# FTDI_USB.net
KiCad netlist of a schematic drawn in Altium Designer
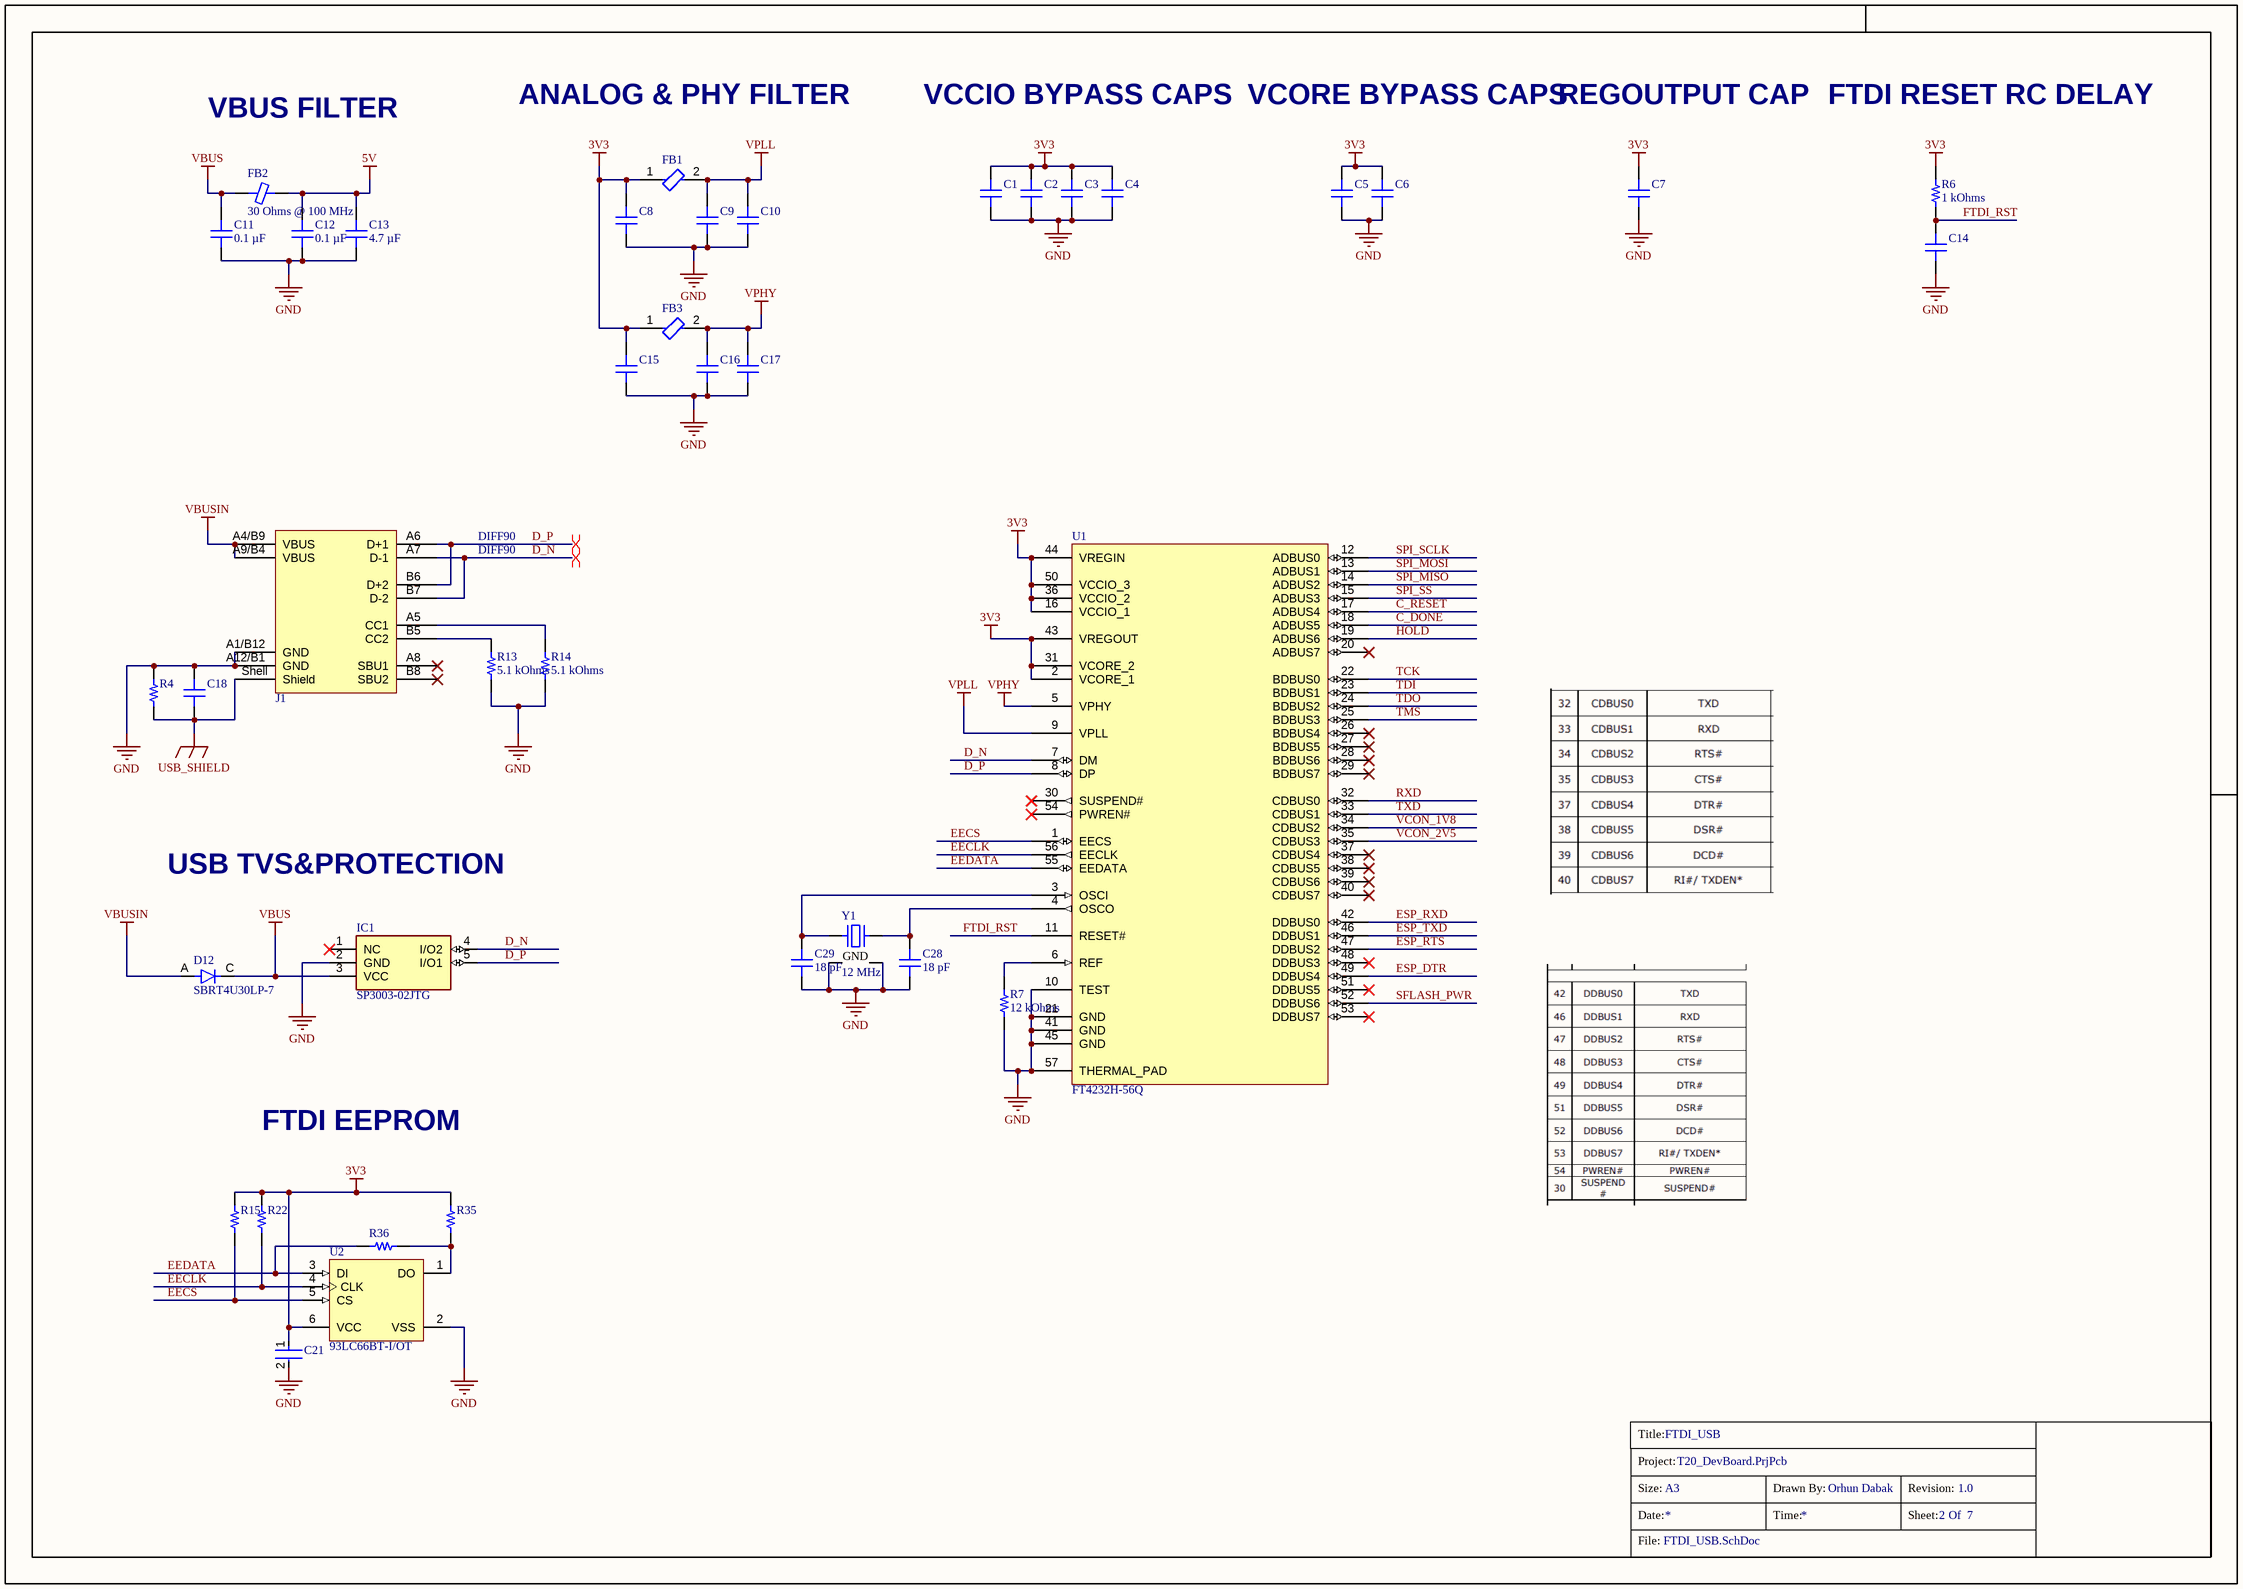
[diagram p0: FTDI_USB.SchDoc]

(export (version "E")
  (design (tool "Eeschema 10.0.6"))
  (components
    (comp (ref "C1")
      (value "0.1 µF")
      (footprint "CAP 0402_1005")
      (description "CAP CER 0.1UF 10V X7R 0402")
      (fields (field (name "PART NUMBER") "CC0402KRX7R6BB104") (field (name "MANUFACTURER") "Yageo"))
      (libsource (lib "Celestial Altium Library - altium_library") (part "Capacitor"))
    )
    (comp (ref "C2")
      (value "0.1 µF")
      (footprint "CAP 0402_1005")
      (description "CAP CER 0.1UF 10V X7R 0402")
      (fields (field (name "PART NUMBER") "CC0402KRX7R6BB104") (field (name "MANUFACTURER") "Yageo"))
      (libsource (lib "Celestial Altium Library - altium_library") (part "Capacitor"))
    )
    (comp (ref "C3")
      (value "0.1 µF")
      (footprint "CAP 0402_1005")
      (description "CAP CER 0.1UF 10V X7R 0402")
      (fields (field (name "PART NUMBER") "CC0402KRX7R6BB104") (field (name "MANUFACTURER") "Yageo"))
      (libsource (lib "Celestial Altium Library - altium_library") (part "Capacitor"))
    )
    (comp (ref "C4")
      (value "0.1 µF")
      (footprint "CAP 0402_1005")
      (description "CAP CER 0.1UF 10V X7R 0402")
      (fields (field (name "PART NUMBER") "CC0402KRX7R6BB104") (field (name "MANUFACTURER") "Yageo"))
      (libsource (lib "Celestial Altium Library - altium_library") (part "Capacitor"))
    )
    (comp (ref "C5")
      (value "0.1 µF")
      (footprint "CAP 0402_1005")
      (description "CAP CER 0.1UF 10V X7R 0402")
      (fields (field (name "PART NUMBER") "CC0402KRX7R6BB104") (field (name "MANUFACTURER") "Yageo"))
      (libsource (lib "Celestial Altium Library - altium_library") (part "Capacitor"))
    )
    (comp (ref "C6")
      (value "0.1 µF")
      (footprint "CAP 0402_1005")
      (description "CAP CER 0.1UF 10V X7R 0402")
      (fields (field (name "PART NUMBER") "CC0402KRX7R6BB104") (field (name "MANUFACTURER") "Yageo"))
      (libsource (lib "Celestial Altium Library - altium_library") (part "Capacitor"))
    )
    (comp (ref "C7")
      (value "4.7 µF")
      (footprint "CAP 0402_1005")
      (description "CAP CER 4.7UF 10V X5R 0402")
      (fields
        (field (name "PART NUMBER") "CL05A475MP5NRNC")
        (field (name "MANUFACTURER") "Samsung Electro-Mechanics")
      )
      (libsource (lib "Celestial Altium Library - altium_library") (part "Capacitor"))
    )
    (comp (ref "C8")
      (value "0.1 µF")
      (footprint "CAP 0402_1005")
      (description "CAP CER 0.1UF 10V X7R 0402")
      (fields (field (name "PART NUMBER") "CC0402KRX7R6BB104") (field (name "MANUFACTURER") "Yageo"))
      (libsource (lib "Celestial Altium Library - altium_library") (part "Capacitor"))
    )
    (comp (ref "C9")
      (value "0.1 µF")
      (footprint "CAP 0402_1005")
      (description "CAP CER 0.1UF 10V X7R 0402")
      (fields (field (name "PART NUMBER") "CC0402KRX7R6BB104") (field (name "MANUFACTURER") "Yageo"))
      (libsource (lib "Celestial Altium Library - altium_library") (part "Capacitor"))
    )
    (comp (ref "C10")
      (value "4.7 µF")
      (footprint "CAP 0402_1005")
      (description "CAP CER 4.7UF 10V X5R 0402")
      (fields
        (field (name "PART NUMBER") "CL05A475MP5NRNC")
        (field (name "MANUFACTURER") "Samsung Electro-Mechanics")
      )
      (libsource (lib "Celestial Altium Library - altium_library") (part "Capacitor"))
    )
    (comp (ref "C11")
      (value "0.1 µF")
      (footprint "CAP 0603_1608")
      (description "CAP CER 0.1UF 25V X7R 0603")
      (fields (field (name "PART NUMBER") "C0603X104M3RAC7867") (field (name "MANUFACTURER") "KEMET"))
      (libsource (lib "Celestial Altium Library - altium_library") (part "Capacitor"))
    )
    (comp (ref "C12")
      (value "0.1 µF")
      (footprint "CAP 0603_1608")
      (description "CAP CER 0.1UF 25V X7R 0603")
      (fields (field (name "PART NUMBER") "C0603X104M3RAC7867") (field (name "MANUFACTURER") "KEMET"))
      (libsource (lib "Celestial Altium Library - altium_library") (part "Capacitor"))
    )
    (comp (ref "C13")
      (value "4.7 µF")
      (footprint "CAP 0603_1608")
      (description "CAP CER 4.7UF 25V X5R 0603")
      (fields
        (field (name "PART NUMBER") "CL10A475KA8NQNC")
        (field (name "MANUFACTURER") "Samsung Electro-Mechanics")
      )
      (libsource (lib "Celestial Altium Library - altium_library") (part "Capacitor"))
    )
    (comp (ref "C14")
      (value "0.1 µF")
      (footprint "CAP 0402_1005")
      (description "CAP CER 0.1UF 10V X7R 0402")
      (fields (field (name "PART NUMBER") "CC0402KRX7R6BB104") (field (name "MANUFACTURER") "Yageo"))
      (libsource (lib "Celestial Altium Library - altium_library") (part "Capacitor"))
    )
    (comp (ref "C15")
      (value "0.1 µF")
      (footprint "CAP 0402_1005")
      (description "CAP CER 0.1UF 10V X7R 0402")
      (fields (field (name "PART NUMBER") "CC0402KRX7R6BB104") (field (name "MANUFACTURER") "Yageo"))
      (libsource (lib "Celestial Altium Library - altium_library") (part "Capacitor"))
    )
    (comp (ref "C16")
      (value "0.1 µF")
      (footprint "CAP 0402_1005")
      (description "CAP CER 0.1UF 10V X7R 0402")
      (fields (field (name "PART NUMBER") "CC0402KRX7R6BB104") (field (name "MANUFACTURER") "Yageo"))
      (libsource (lib "Celestial Altium Library - altium_library") (part "Capacitor"))
    )
    (comp (ref "C17")
      (value "4.7 µF")
      (footprint "CAP 0402_1005")
      (description "CAP CER 4.7UF 10V X5R 0402")
      (fields
        (field (name "PART NUMBER") "CL05A475MP5NRNC")
        (field (name "MANUFACTURER") "Samsung Electro-Mechanics")
      )
      (libsource (lib "Celestial Altium Library - altium_library") (part "Capacitor"))
    )
    (comp (ref "C18")
      (value "10000 pF")
      (footprint "CAP 0402_1005")
      (description "CAP CER 10000PF 100V X7R 0402")
      (fields (field (name "PART NUMBER") "CC0402KRX7R0BB103") (field (name "MANUFACTURER") "Yageo"))
      (libsource (lib "Celestial Altium Library - altium_library") (part "Capacitor"))
    )
    (comp (ref "C21")
      (value "EMK105B7104KV-F")
      (footprint "FP-0402-L_1_0_0_05-W_0_5-MFG")
      (description "None")
      (fields (field (name "TOLERANCE") "10%"))
      (libsource (lib "Altium Content Vault") (part "b4654b650e69147ec39a6b967a45e02"))
    )
    (comp (ref "C28")
      (value "18 pF")
      (footprint "CAP 0402_1005")
      (description "CAP CER 18PF 50V C0G/NP0 0402")
      (fields (field (name "PART NUMBER") "C0402C180J5GACAUTO") (field (name "MANUFACTURER") "KEMET"))
      (libsource (lib "Celestial Altium Library - altium_library") (part "Capacitor"))
    )
    (comp (ref "C29")
      (value "18 pF")
      (footprint "CAP 0402_1005")
      (description "CAP CER 18PF 50V C0G/NP0 0402")
      (fields (field (name "PART NUMBER") "C0402C180J5GACAUTO") (field (name "MANUFACTURER") "KEMET"))
      (libsource (lib "Celestial Altium Library - altium_library") (part "Capacitor"))
    )
    (comp (ref "D12")
      (value "SBRT4U30LP-7")
      (footprint "DIO_SBRT4U30LP-7:DIO_SBRT4U30LP-7")
      (description "Diode Super Barrier 30 V 4A Surface Mount U-DFN2020-2")
      (fields (field (name "MF") "Diodes Inc."))
      (libsource (lib "SBRT4U30LP-7") (part "SBRT4U30LP-7"))
    )
    (comp (ref "FB1")
      (value "BLM15AX601SN1D")
      (footprint "FP-BLM15-0_05-IPC_B")
      (description "Chip Ferrite Bead, 0402, 600Ω @ 100MHz, 0.34Ω, 25%, 500mA")
      (fields (field (name "TOLERANCE") "25%"))
      (libsource (lib "Altium Content Vault") (part "5f30dd21d616792df468990f7003faa"))
    )
    (comp (ref "FB2")
      (value "30 Ohms @ 100 MHz")
      (footprint "FER 0805_2012")
      (description "FERRITE BEAD 30 OHM 0805 1LN")
      (fields
        (field (name "PART NUMBER") "BLM21PG300SN1D")
        (field (name "MANUFACTURER") "Murata Electronics")
      )
      (libsource (lib "Celestial Altium Library - altium_library") (part "Ferrite Chip"))
    )
    (comp (ref "FB3")
      (value "BLM15AX601SN1D")
      (footprint "FP-BLM15-0_05-IPC_B")
      (description "Chip Ferrite Bead, 0402, 600Ω @ 100MHz, 0.34Ω, 25%, 500mA")
      (fields (field (name "TOLERANCE") "25%"))
      (libsource (lib "Altium Content Vault") (part "5f30dd21d616792df468990f7003faa"))
    )
    (comp (ref "IC1")
      (value "SP3003-02JTG")
      (footprint "SamacSys:SOT65P220X110-5N")
      (description "Integrated Circuit")
      (fields (field (name "MOUSER PART NUMBER") "576-SP3003-02JTG"))
      (libsource (lib "*") (part "SP3003-02JTG"))
    )
    (comp (ref "J1")
      (value "629722000214")
      (footprint "629722000214")
      (description "WR-USB 2.0 Type C, Receptacle, Horizontal, SMT")
      (fields (field (name "MANUFACTURER") "Wurth Elektronik"))
      (libsource (lib "Altium_WR-USB (rev22b)") (part "629722000214"))
    )
    (comp (ref "R4")
      (value "1 MOhms")
      (footprint "RES 0402_1005")
      (description "RES SMD 1M OHM 1% 1/16W 0402")
      (fields (field (name "PART NUMBER") "AC0402FR-071ML") (field (name "MANUFACTURER") "Yageo"))
      (libsource (lib "Celestial Altium Library - altium_library") (part "Resistor"))
    )
    (comp (ref "R6")
      (value "1 kOhms")
      (footprint "RES 0402_1005")
      (description "RES SMD 1K OHM 5% 1/16W 0402")
      (fields (field (name "PART NUMBER") "RC0402JR-071KP") (field (name "MANUFACTURER") "Yageo"))
      (libsource (lib "Celestial Altium Library - altium_library") (part "Resistor"))
    )
    (comp (ref "R7")
      (value "12 kOhms")
      (footprint "RES 0402_1005")
      (description "RES SMD 12K OHM 0.1% 1/16W 0402")
      (fields
        (field (name "PART NUMBER") "CPF0402B12KE1")
        (field (name "MANUFACTURER") "TE Connectivity Passive Product")
      )
      (libsource (lib "Celestial Altium Library - altium_library") (part "Resistor"))
    )
    (comp (ref "R13")
      (value "5.1 kOhms")
      (footprint "RES 0402_1005")
      (description "RES SMD 5.1K OHM 5% 1/16W 0402")
      (fields (field (name "PART NUMBER") "AC0402JR-075K1L") (field (name "MANUFACTURER") "Yageo"))
      (libsource (lib "Celestial Altium Library - altium_library") (part "Resistor"))
    )
    (comp (ref "R14")
      (value "5.1 kOhms")
      (footprint "RES 0402_1005")
      (description "RES SMD 5.1K OHM 5% 1/16W 0402")
      (fields (field (name "PART NUMBER") "AC0402JR-075K1L") (field (name "MANUFACTURER") "Yageo"))
      (libsource (lib "Celestial Altium Library - altium_library") (part "Resistor"))
    )
    (comp (ref "R15")
      (value "10 kOhms")
      (footprint "RES 0402_1005")
      (description "RES 10K OHM 0.1% 1/10W 0402")
      (fields
        (field (name "PART NUMBER") "RP73PF1E10KBTD")
        (field (name "MANUFACTURER") "TE Connectivity Passive Product")
      )
      (libsource (lib "Celestial Altium Library - altium_library") (part "Resistor"))
    )
    (comp (ref "R22")
      (value "10 kOhms")
      (footprint "RES 0402_1005")
      (description "RES 10K OHM 0.1% 1/10W 0402")
      (fields
        (field (name "PART NUMBER") "RP73PF1E10KBTD")
        (field (name "MANUFACTURER") "TE Connectivity Passive Product")
      )
      (libsource (lib "Celestial Altium Library - altium_library") (part "Resistor"))
    )
    (comp (ref "R35")
      (value "10 kOhms")
      (footprint "RES 0402_1005")
      (description "RES 10K OHM 0.1% 1/10W 0402")
      (fields
        (field (name "PART NUMBER") "RP73PF1E10KBTD")
        (field (name "MANUFACTURER") "TE Connectivity Passive Product")
      )
      (libsource (lib "Celestial Altium Library - altium_library") (part "Resistor"))
    )
    (comp (ref "R36")
      (value "2.2 kOhms")
      (footprint "RES 0402_1005")
      (description "RES 2.2K OHM 0.1% 1/10W 0402")
      (fields (field (name "PART NUMBER") "TNPW04022K20BYEP") (field (name "MANUFACTURER") "Vishay Dale"))
      (libsource (lib "Celestial Altium Library - altium_library") (part "Resistor"))
    )
    (comp (ref "U1")
      (value "FT4232H-56Q")
      (footprint "QFN50P800X800X100-57N-D")
      (description "USB Bridge, USB to UART,FIFO USB 2.0 FIFO Interface 56-VQFN (8x8)")
      (fields (field (name "MANUFACTURER") "FTDI, Future Technology Devices International Ltd"))
      (libsource (lib "T8_devkit_PCB") (part "FT4232H-56Q"))
    )
    (comp (ref "U2")
      (value "93LC66BT-I/OT")
      (footprint "SOT-23-OT6_N")
      (description "Microwire Serial EEPROM Family, 2.5Vto 5.5V' 2 MHz, -40°Cto 125°C, SOT-23-6, RoHS")
      (libsource (lib "Kocaeli University") (part "MEM-SEEPROM-93AA46B-OT-6"))
    )
    (comp (ref "Y1")
      (value "12 MHz")
      (footprint "NDK NX3225GA")
      (description "CRYSTAL 12.0000MHZ 8PF SMD")
      (fields
        (field (name "PART NUMBER") "NX3225GA-12MHZ-STD-CRG-2")
        (field (name "MANUFACTURER") "NDK America, Inc.")
      )
      (libsource (lib "Celestial Altium Library - altium_library") (part "NDK Crystal NX3225GA"))
    )
  )
  (nets
    (net (code "1") (name "/C_DONE") (class "Default")
      (node (ref "U1") (pin "18") (pinfunction "ADBUS5_18") (pintype "bidirectional"))
    )
    (net (code "2") (name "/C_RESET") (class "Default")
      (node (ref "U1") (pin "17") (pinfunction "ADBUS4_17") (pintype "bidirectional"))
    )
    (net (code "3") (name "/D_N") (class "Default")
      (node (ref "IC1") (pin "4") (pinfunction "I/O2_4") (pintype "bidirectional"))
      (node (ref "J1") (pin "A7") (pinfunction "D-1_A7") (pintype "passive"))
      (node (ref "J1") (pin "B7") (pinfunction "D-2_B7") (pintype "passive"))
      (node (ref "U1") (pin "7") (pinfunction "DM_7") (pintype "bidirectional"))
    )
    (net (code "4") (name "/D_P") (class "Default")
      (node (ref "IC1") (pin "5") (pinfunction "I/O1_5") (pintype "bidirectional"))
      (node (ref "J1") (pin "A6") (pinfunction "D+1_A6") (pintype "passive"))
      (node (ref "J1") (pin "B6") (pinfunction "D+2_B6") (pintype "passive"))
      (node (ref "U1") (pin "8") (pinfunction "DP_8") (pintype "bidirectional"))
    )
    (net (code "5") (name "/EECLK") (class "Default")
      (node (ref "R22") (pin "1") (pinfunction "1_1") (pintype "passive"))
      (node (ref "U1") (pin "56") (pinfunction "EECLK_56") (pintype "output"))
      (node (ref "U2") (pin "4") (pinfunction "CLK_4") (pintype "input"))
    )
    (net (code "6") (name "/EECS") (class "Default")
      (node (ref "R15") (pin "1") (pinfunction "1_1") (pintype "passive"))
      (node (ref "U1") (pin "1") (pinfunction "EECS_1") (pintype "bidirectional"))
      (node (ref "U2") (pin "5") (pinfunction "CS_5") (pintype "input"))
    )
    (net (code "7") (name "/EEDATA") (class "Default")
      (node (ref "R36") (pin "1") (pinfunction "1_1") (pintype "passive"))
      (node (ref "U1") (pin "55") (pinfunction "EEDATA_55") (pintype "bidirectional"))
      (node (ref "U2") (pin "3") (pinfunction "DI_3") (pintype "input"))
    )
    (net (code "8") (name "/ESP_DTR") (class "Default")
      (node (ref "U1") (pin "49") (pinfunction "DDBUS4_49") (pintype "bidirectional"))
    )
    (net (code "9") (name "/ESP_RTS") (class "Default")
      (node (ref "U1") (pin "47") (pinfunction "DDBUS2_47") (pintype "bidirectional"))
    )
    (net (code "10") (name "/ESP_RXD") (class "Default")
      (node (ref "U1") (pin "42") (pinfunction "DDBUS0_42") (pintype "bidirectional"))
    )
    (net (code "11") (name "/ESP_TXD") (class "Default")
      (node (ref "U1") (pin "46") (pinfunction "DDBUS1_46") (pintype "bidirectional"))
    )
    (net (code "12") (name "/FTDI_RST") (class "Default")
      (node (ref "C14") (pin "2") (pinfunction "2_2") (pintype "passive"))
      (node (ref "R6") (pin "1") (pinfunction "1_1") (pintype "passive"))
      (node (ref "U1") (pin "11") (pinfunction "RESET#_11") (pintype "passive"))
    )
    (net (code "13") (name "/HOLD") (class "Default")
      (node (ref "U1") (pin "19") (pinfunction "ADBUS6_19") (pintype "bidirectional"))
    )
    (net (code "14") (name "/RXD") (class "Default")
      (node (ref "U1") (pin "32") (pinfunction "CDBUS0_32") (pintype "bidirectional"))
    )
    (net (code "15") (name "/SFLASH_PWR") (class "Default")
      (node (ref "U1") (pin "52") (pinfunction "DDBUS6_52") (pintype "bidirectional"))
    )
    (net (code "16") (name "/SPI_MISO") (class "Default")
      (node (ref "U1") (pin "14") (pinfunction "ADBUS2_14") (pintype "bidirectional"))
    )
    (net (code "17") (name "/SPI_MOSI") (class "Default")
      (node (ref "U1") (pin "13") (pinfunction "ADBUS1_13") (pintype "bidirectional"))
    )
    (net (code "18") (name "/SPI_SCLK") (class "Default")
      (node (ref "U1") (pin "12") (pinfunction "ADBUS0_12") (pintype "bidirectional"))
    )
    (net (code "19") (name "/SPI_SS") (class "Default")
      (node (ref "U1") (pin "15") (pinfunction "ADBUS3_15") (pintype "bidirectional"))
    )
    (net (code "20") (name "/TCK") (class "Default")
      (node (ref "U1") (pin "22") (pinfunction "BDBUS0_22") (pintype "bidirectional"))
    )
    (net (code "21") (name "/TDI") (class "Default")
      (node (ref "U1") (pin "23") (pinfunction "BDBUS1_23") (pintype "bidirectional"))
    )
    (net (code "22") (name "/TDO") (class "Default")
      (node (ref "U1") (pin "24") (pinfunction "BDBUS2_24") (pintype "bidirectional"))
    )
    (net (code "23") (name "/TMS") (class "Default")
      (node (ref "U1") (pin "25") (pinfunction "BDBUS3_25") (pintype "bidirectional"))
    )
    (net (code "24") (name "/TXD") (class "Default")
      (node (ref "U1") (pin "33") (pinfunction "CDBUS1_33") (pintype "bidirectional"))
    )
    (net (code "25") (name "/VCON_1V8") (class "Default")
      (node (ref "U1") (pin "34") (pinfunction "CDBUS2_34") (pintype "bidirectional"))
    )
    (net (code "26") (name "/VCON_2V5") (class "Default")
      (node (ref "U1") (pin "35") (pinfunction "CDBUS3_35") (pintype "bidirectional"))
    )
    (net (code "27") (name "3V3") (class "Default")
      (node (ref "C1") (pin "2") (pinfunction "2_2") (pintype "passive"))
      (node (ref "C15") (pin "2") (pinfunction "2_2") (pintype "passive"))
      (node (ref "C2") (pin "2") (pinfunction "2_2") (pintype "passive"))
      (node (ref "C21") (pin "1") (pinfunction "1_1") (pintype "passive"))
      (node (ref "C3") (pin "2") (pinfunction "2_2") (pintype "passive"))
      (node (ref "C4") (pin "2") (pinfunction "2_2") (pintype "passive"))
      (node (ref "C5") (pin "2") (pinfunction "2_2") (pintype "passive"))
      (node (ref "C6") (pin "2") (pinfunction "2_2") (pintype "passive"))
      (node (ref "C7") (pin "2") (pinfunction "2_2") (pintype "passive"))
      (node (ref "C8") (pin "2") (pinfunction "2_2") (pintype "passive"))
      (node (ref "FB1") (pin "1") (pinfunction "1_1") (pintype "passive"))
      (node (ref "FB3") (pin "1") (pinfunction "1_1") (pintype "passive"))
      (node (ref "R15") (pin "2") (pinfunction "2_2") (pintype "passive"))
      (node (ref "R22") (pin "2") (pinfunction "2_2") (pintype "passive"))
      (node (ref "R35") (pin "2") (pinfunction "2_2") (pintype "passive"))
      (node (ref "R6") (pin "2") (pinfunction "2_2") (pintype "passive"))
      (node (ref "U1") (pin "16") (pinfunction "VCCIO_1_16") (pintype "power_in"))
      (node (ref "U1") (pin "2") (pinfunction "VCORE_1_2") (pintype "power_in"))
      (node (ref "U1") (pin "31") (pinfunction "VCORE_2_31") (pintype "power_in"))
      (node (ref "U1") (pin "36") (pinfunction "VCCIO_2_36") (pintype "power_in"))
      (node (ref "U1") (pin "43") (pinfunction "VREGOUT_43") (pintype "power_in"))
      (node (ref "U1") (pin "44") (pinfunction "VREGIN_44") (pintype "power_in"))
      (node (ref "U1") (pin "50") (pinfunction "VCCIO_3_50") (pintype "power_in"))
      (node (ref "U2") (pin "6") (pinfunction "VCC_6") (pintype "power_in"))
    )
    (net (code "28") (name "5V") (class "Default")
      (node (ref "C12") (pin "2") (pinfunction "2_2") (pintype "passive"))
      (node (ref "C13") (pin "2") (pinfunction "2_2") (pintype "passive"))
      (node (ref "FB2") (pin "2") (pinfunction "2_2") (pintype "passive"))
    )
    (net (code "29") (name "GND") (class "Default")
      (node (ref "C1") (pin "1") (pinfunction "1_1") (pintype "passive"))
      (node (ref "C10") (pin "1") (pinfunction "1_1") (pintype "passive"))
      (node (ref "C11") (pin "1") (pinfunction "1_1") (pintype "passive"))
      (node (ref "C12") (pin "1") (pinfunction "1_1") (pintype "passive"))
      (node (ref "C13") (pin "1") (pinfunction "1_1") (pintype "passive"))
      (node (ref "C14") (pin "1") (pinfunction "1_1") (pintype "passive"))
      (node (ref "C15") (pin "1") (pinfunction "1_1") (pintype "passive"))
      (node (ref "C16") (pin "1") (pinfunction "1_1") (pintype "passive"))
      (node (ref "C17") (pin "1") (pinfunction "1_1") (pintype "passive"))
      (node (ref "C18") (pin "2") (pinfunction "2_2") (pintype "passive"))
      (node (ref "C2") (pin "1") (pinfunction "1_1") (pintype "passive"))
      (node (ref "C21") (pin "2") (pinfunction "2_2") (pintype "passive"))
      (node (ref "C28") (pin "1") (pinfunction "1_1") (pintype "passive"))
      (node (ref "C29") (pin "1") (pinfunction "1_1") (pintype "passive"))
      (node (ref "C3") (pin "1") (pinfunction "1_1") (pintype "passive"))
      (node (ref "C4") (pin "1") (pinfunction "1_1") (pintype "passive"))
      (node (ref "C5") (pin "1") (pinfunction "1_1") (pintype "passive"))
      (node (ref "C6") (pin "1") (pinfunction "1_1") (pintype "passive"))
      (node (ref "C7") (pin "1") (pinfunction "1_1") (pintype "passive"))
      (node (ref "C8") (pin "1") (pinfunction "1_1") (pintype "passive"))
      (node (ref "C9") (pin "1") (pinfunction "1_1") (pintype "passive"))
      (node (ref "IC1") (pin "2") (pinfunction "GND_2") (pintype "power_in"))
      (node (ref "J1") (pin "A1/B12") (pinfunction "GND_A1/B12") (pintype "passive"))
      (node (ref "J1") (pin "A12/B1") (pinfunction "GND_A12/B1") (pintype "passive"))
      (node (ref "R13") (pin "1") (pinfunction "1_1") (pintype "passive"))
      (node (ref "R14") (pin "1") (pinfunction "1_1") (pintype "passive"))
      (node (ref "R4") (pin "2") (pinfunction "2_2") (pintype "passive"))
      (node (ref "R7") (pin "1") (pinfunction "1_1") (pintype "passive"))
      (node (ref "U1") (pin "10") (pinfunction "TEST_10") (pintype "passive"))
      (node (ref "U1") (pin "21") (pinfunction "GND_21") (pintype "power_in"))
      (node (ref "U1") (pin "41") (pinfunction "GND_41") (pintype "power_in"))
      (node (ref "U1") (pin "45") (pinfunction "GND_45") (pintype "power_in"))
      (node (ref "U1") (pin "57") (pinfunction "THERMAL_PAD_57") (pintype "passive"))
      (node (ref "U2") (pin "2") (pinfunction "VSS_2") (pintype "power_in"))
      (node (ref "Y1") (pin "2") (pinfunction "GND_2") (pintype "passive"))
      (node (ref "Y1") (pin "4") (pinfunction "GND_4") (pintype "passive"))
    )
    (net (code "30") (name "Net-(J1-CC1)") (class "Default")
      (node (ref "J1") (pin "A5") (pinfunction "CC1_A5") (pintype "passive"))
      (node (ref "R14") (pin "2") (pinfunction "2_2") (pintype "passive"))
    )
    (net (code "31") (name "Net-(J1-CC2)") (class "Default")
      (node (ref "J1") (pin "B5") (pinfunction "CC2_B5") (pintype "passive"))
      (node (ref "R13") (pin "2") (pinfunction "2_2") (pintype "passive"))
    )
    (net (code "32") (name "Net-(U1-OSCI)") (class "Default")
      (node (ref "C29") (pin "2") (pinfunction "2_2") (pintype "passive"))
      (node (ref "U1") (pin "3") (pinfunction "OSCI_3") (pintype "input"))
      (node (ref "Y1") (pin "1") (pinfunction "1_1") (pintype "passive"))
    )
    (net (code "33") (name "Net-(U1-OSCO)") (class "Default")
      (node (ref "C28") (pin "2") (pinfunction "2_2") (pintype "passive"))
      (node (ref "U1") (pin "4") (pinfunction "OSCO_4") (pintype "output"))
      (node (ref "Y1") (pin "3") (pinfunction "3_3") (pintype "passive"))
    )
    (net (code "34") (name "Net-(U1-REF)") (class "Default")
      (node (ref "R7") (pin "2") (pinfunction "2_2") (pintype "passive"))
      (node (ref "U1") (pin "6") (pinfunction "REF_6") (pintype "input"))
    )
    (net (code "35") (name "Net-(U2-DO)") (class "Default")
      (node (ref "R35") (pin "1") (pinfunction "1_1") (pintype "passive"))
      (node (ref "R36") (pin "2") (pinfunction "2_2") (pintype "passive"))
      (node (ref "U2") (pin "1") (pinfunction "DO_1") (pintype "tri_state"))
    )
    (net (code "36") (name "USB_SHIELD") (class "Default")
      (node (ref "C18") (pin "1") (pinfunction "1_1") (pintype "passive"))
      (node (ref "J1") (pin "Shell") (pinfunction "Shield_Shell") (pintype "passive"))
      (node (ref "R4") (pin "1") (pinfunction "1_1") (pintype "passive"))
    )
    (net (code "37") (name "VBUS") (class "Default")
      (node (ref "C11") (pin "2") (pinfunction "2_2") (pintype "passive"))
      (node (ref "D12") (pin "C") (pinfunction "K_C") (pintype "passive"))
      (node (ref "FB2") (pin "1") (pinfunction "1_1") (pintype "passive"))
      (node (ref "IC1") (pin "3") (pinfunction "VCC_3") (pintype "power_in"))
    )
    (net (code "38") (name "VBUSIN") (class "Default")
      (node (ref "D12") (pin "A") (pinfunction "A_A") (pintype "passive"))
      (node (ref "J1") (pin "A4/B9") (pinfunction "VBUS_A4/B9") (pintype "passive"))
      (node (ref "J1") (pin "A9/B4") (pinfunction "VBUS_A9/B4") (pintype "passive"))
    )
    (net (code "39") (name "VPHY") (class "Default")
      (node (ref "C16") (pin "2") (pinfunction "2_2") (pintype "passive"))
      (node (ref "C17") (pin "2") (pinfunction "2_2") (pintype "passive"))
      (node (ref "FB3") (pin "2") (pinfunction "2_2") (pintype "passive"))
      (node (ref "U1") (pin "5") (pinfunction "VPHY_5") (pintype "power_in"))
    )
    (net (code "40") (name "VPLL") (class "Default")
      (node (ref "C10") (pin "2") (pinfunction "2_2") (pintype "passive"))
      (node (ref "C9") (pin "2") (pinfunction "2_2") (pintype "passive"))
      (node (ref "FB1") (pin "2") (pinfunction "2_2") (pintype "passive"))
      (node (ref "U1") (pin "9") (pinfunction "VPLL_9") (pintype "power_in"))
    )
    (net (code "41") (name "unconnected-(IC1-NC-Pad1)") (class "Default")
      (node (ref "IC1") (pin "1") (pinfunction "NC_1") (pintype "passive+no_connect"))
    )
    (net (code "42") (name "unconnected-(J1-SBU1-PadA8)") (class "Default")
      (node (ref "J1") (pin "A8") (pinfunction "SBU1_A8") (pintype "passive+no_connect"))
    )
    (net (code "43") (name "unconnected-(J1-SBU2-PadB8)") (class "Default")
      (node (ref "J1") (pin "B8") (pinfunction "SBU2_B8") (pintype "passive+no_connect"))
    )
    (net (code "44") (name "unconnected-(U1-ADBUS7-Pad20)") (class "Default")
      (node (ref "U1") (pin "20") (pinfunction "ADBUS7_20") (pintype "bidirectional+no_connect"))
    )
    (net (code "45") (name "unconnected-(U1-BDBUS4-Pad26)") (class "Default")
      (node (ref "U1") (pin "26") (pinfunction "BDBUS4_26") (pintype "bidirectional+no_connect"))
    )
    (net (code "46") (name "unconnected-(U1-BDBUS5-Pad27)") (class "Default")
      (node (ref "U1") (pin "27") (pinfunction "BDBUS5_27") (pintype "bidirectional+no_connect"))
    )
    (net (code "47") (name "unconnected-(U1-BDBUS6-Pad28)") (class "Default")
      (node (ref "U1") (pin "28") (pinfunction "BDBUS6_28") (pintype "bidirectional+no_connect"))
    )
    (net (code "48") (name "unconnected-(U1-BDBUS7-Pad29)") (class "Default")
      (node (ref "U1") (pin "29") (pinfunction "BDBUS7_29") (pintype "bidirectional+no_connect"))
    )
    (net (code "49") (name "unconnected-(U1-CDBUS4-Pad37)") (class "Default")
      (node (ref "U1") (pin "37") (pinfunction "CDBUS4_37") (pintype "bidirectional+no_connect"))
    )
    (net (code "50") (name "unconnected-(U1-CDBUS5-Pad38)") (class "Default")
      (node (ref "U1") (pin "38") (pinfunction "CDBUS5_38") (pintype "bidirectional+no_connect"))
    )
    (net (code "51") (name "unconnected-(U1-CDBUS6-Pad39)") (class "Default")
      (node (ref "U1") (pin "39") (pinfunction "CDBUS6_39") (pintype "bidirectional+no_connect"))
    )
    (net (code "52") (name "unconnected-(U1-CDBUS7-Pad40)") (class "Default")
      (node (ref "U1") (pin "40") (pinfunction "CDBUS7_40") (pintype "bidirectional+no_connect"))
    )
    (net (code "53") (name "unconnected-(U1-DDBUS3-Pad48)") (class "Default")
      (node (ref "U1") (pin "48") (pinfunction "DDBUS3_48") (pintype "bidirectional+no_connect"))
    )
    (net (code "54") (name "unconnected-(U1-DDBUS5-Pad51)") (class "Default")
      (node (ref "U1") (pin "51") (pinfunction "DDBUS5_51") (pintype "bidirectional+no_connect"))
    )
    (net (code "55") (name "unconnected-(U1-DDBUS7-Pad53)") (class "Default")
      (node (ref "U1") (pin "53") (pinfunction "DDBUS7_53") (pintype "bidirectional+no_connect"))
    )
    (net (code "56") (name "unconnected-(U1-PWREN#-Pad54)") (class "Default")
      (node (ref "U1") (pin "54") (pinfunction "PWREN#_54") (pintype "output+no_connect"))
    )
    (net (code "57") (name "unconnected-(U1-SUSPEND#-Pad30)") (class "Default")
      (node (ref "U1") (pin "30") (pinfunction "SUSPEND#_30") (pintype "output+no_connect"))
    )
  )
)
